# USB2JTAG.net
KiCad netlist of a schematic drawn in Altium Designer
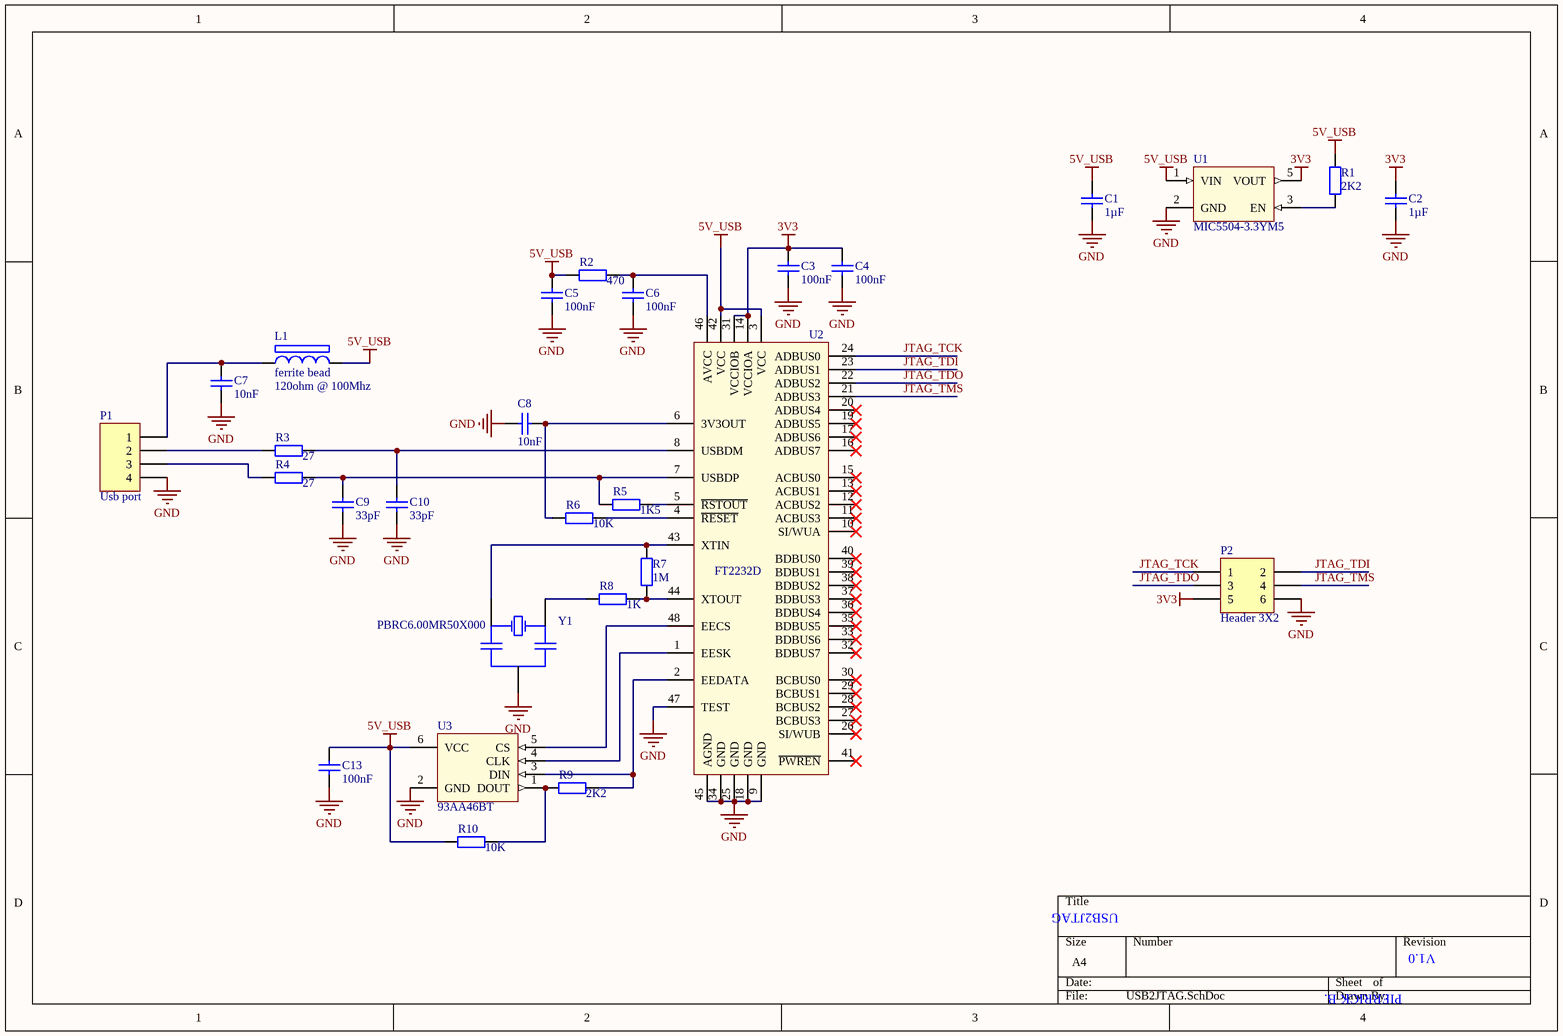
[diagram p0: USB2JTAG.SchDoc]

(export (version "E")
  (design (tool "Eeschema 10.0.6"))
  (components
    (comp (ref "C1")
      (value "1µF")
      (footprint "C0402")
      (description "Capacitor")
      (fields (field (name "Comment") "Cap") (field (name "PUBLISHER") "Altium Limited"))
      (libsource (lib "LIBRARY IGREBOT") (part "Cap"))
    )
    (comp (ref "C2")
      (value "1µF")
      (footprint "C0402")
      (description "Capacitor")
      (fields (field (name "Comment") "Cap") (field (name "PUBLISHER") "Altium Limited"))
      (libsource (lib "LIBRARY IGREBOT") (part "Cap"))
    )
    (comp (ref "C3")
      (value "100nF")
      (footprint "C0402")
      (description "Capacitor")
      (fields (field (name "Comment") "Cap") (field (name "PUBLISHER") "Altium Limited"))
      (libsource (lib "LIBRARY IGREBOT") (part "Cap"))
    )
    (comp (ref "C4")
      (value "100nF")
      (footprint "C0402")
      (description "Capacitor")
      (fields (field (name "Comment") "Cap") (field (name "PUBLISHER") "Altium Limited"))
      (libsource (lib "LIBRARY IGREBOT") (part "Cap"))
    )
    (comp (ref "C5")
      (value "100nF")
      (footprint "C0402")
      (description "Capacitor")
      (fields (field (name "Comment") "Cap") (field (name "PUBLISHER") "Altium Limited"))
      (libsource (lib "LIBRARY IGREBOT") (part "Cap"))
    )
    (comp (ref "C6")
      (value "100nF")
      (footprint "C0402")
      (description "Capacitor")
      (fields (field (name "Comment") "Cap") (field (name "PUBLISHER") "Altium Limited"))
      (libsource (lib "LIBRARY IGREBOT") (part "Cap"))
    )
    (comp (ref "C7")
      (value "10nF")
      (footprint "C0402")
      (description "Capacitor")
      (fields (field (name "Comment") "Cap") (field (name "PUBLISHER") "Altium Limited"))
      (libsource (lib "LIBRARY IGREBOT") (part "Cap"))
    )
    (comp (ref "C8")
      (value "10nF")
      (footprint "C0402")
      (description "Capacitor")
      (fields (field (name "Comment") "Cap") (field (name "PUBLISHER") "Altium Limited"))
      (libsource (lib "LIBRARY IGREBOT") (part "Cap"))
    )
    (comp (ref "C9")
      (value "33pF")
      (footprint "C0402")
      (description "Capacitor")
      (fields (field (name "Comment") "Cap") (field (name "PUBLISHER") "Altium Limited"))
      (libsource (lib "LIBRARY IGREBOT") (part "Cap"))
    )
    (comp (ref "C10")
      (value "33pF")
      (footprint "C0402")
      (description "Capacitor")
      (fields (field (name "Comment") "Cap") (field (name "PUBLISHER") "Altium Limited"))
      (libsource (lib "LIBRARY IGREBOT") (part "Cap"))
    )
    (comp (ref "C13")
      (value "100nF")
      (footprint "C0402")
      (description "Capacitor")
      (fields (field (name "Comment") "Cap") (field (name "PUBLISHER") "Altium Limited"))
      (libsource (lib "LIBRARY IGREBOT") (part "Cap"))
    )
    (comp (ref "L1")
      (value "ferrite bead")
      (footprint "0402")
      (fields (field (name "ALTIUM_VALUE") "120ohm @ 100Mhz") (field (name "PUBLISHER") "Altium Limited"))
      (libsource (lib "LIBRARY IGREBOT") (part "ferrite bead"))
    )
    (comp (ref "P1")
      (value "Usb port")
      (footprint "480371000")
      (libsource (lib "LIBRARY IGREBOT") (part "Usb port"))
    )
    (comp (ref "P2")
      (value "Header 3X2")
      (footprint "minitek127-6way")
      (description "Header, 6-Pin, Dual row")
      (fields (field (name "PUBLISHER") "Altium Limited"))
      (libsource (lib "LIBRARY IGREBOT") (part "Header 3X2"))
    )
    (comp (ref "R1")
      (value "2K2")
      (footprint "0402")
      (description "Resistor")
      (fields (field (name "Comment") "Res2") (field (name "PUBLISHER") "Altium Limited"))
      (libsource (lib "") (part "Res2_1"))
    )
    (comp (ref "R2")
      (value "470")
      (footprint "0402")
      (description "Resistor")
      (fields (field (name "Comment") "Res2") (field (name "PUBLISHER") "Altium Limited"))
      (libsource (lib "LIBRARY IGREBOT") (part "Res2"))
    )
    (comp (ref "R3")
      (value "27")
      (footprint "0402")
      (description "Resistor")
      (fields (field (name "Comment") "Res2") (field (name "PUBLISHER") "Altium Limited"))
      (libsource (lib "LIBRARY IGREBOT") (part "Res2"))
    )
    (comp (ref "R4")
      (value "27")
      (footprint "0402")
      (description "Resistor")
      (fields (field (name "Comment") "Res2") (field (name "PUBLISHER") "Altium Limited"))
      (libsource (lib "LIBRARY IGREBOT") (part "Res2"))
    )
    (comp (ref "R5")
      (value "1K5")
      (footprint "0402")
      (description "Resistor")
      (fields (field (name "Comment") "Res2") (field (name "PUBLISHER") "Altium Limited"))
      (libsource (lib "") (part "Res2_2"))
    )
    (comp (ref "R6")
      (value "10K")
      (footprint "0402")
      (description "Resistor")
      (fields (field (name "Comment") "Res2") (field (name "PUBLISHER") "Altium Limited"))
      (libsource (lib "LIBRARY IGREBOT") (part "Res2"))
    )
    (comp (ref "R7")
      (value "1M")
      (footprint "0402")
      (description "Resistor")
      (fields (field (name "Comment") "Res2") (field (name "PUBLISHER") "Altium Limited"))
      (libsource (lib "") (part "Res2_1"))
    )
    (comp (ref "R8")
      (value "1K")
      (footprint "0402")
      (description "Resistor")
      (fields (field (name "Comment") "Res2") (field (name "PUBLISHER") "Altium Limited"))
      (libsource (lib "LIBRARY IGREBOT") (part "Res2"))
    )
    (comp (ref "R9")
      (value "2K2")
      (footprint "0402")
      (description "Resistor")
      (fields (field (name "Comment") "Res2") (field (name "PUBLISHER") "Altium Limited"))
      (libsource (lib "LIBRARY IGREBOT") (part "Res2"))
    )
    (comp (ref "R10")
      (value "10K")
      (footprint "0402")
      (description "Resistor")
      (fields (field (name "Comment") "Res2") (field (name "PUBLISHER") "Altium Limited"))
      (libsource (lib "LIBRARY IGREBOT") (part "Res2"))
    )
    (comp (ref "U1")
      (value "MIC5504-3.3YM5")
      (footprint "SOT23-5_M")
      (libsource (lib "LIBRARY IGREBOT") (part "MIC5504-3.3YM5"))
    )
    (comp (ref "U2")
      (value "FT2232D")
      (footprint "LQFP-48")
      (libsource (lib "LIBRARY IGREBOT") (part "FT2232D"))
    )
    (comp (ref "U3")
      (value "93AA46BT")
      (footprint "SOT23-6_M")
      (libsource (lib "LIBRARY IGREBOT") (part "93AA46BT"))
    )
    (comp (ref "Y1")
      (value "PBRC6.00MR50X000")
      (footprint "PBRC_M")
      (libsource (lib "LIBRARY IGREBOT") (part "PBRC12.00HR50X0RZ"))
    )
  )
  (nets
    (net (code "1") (name "/JTAG_TCK") (class "Default")
      (node (ref "P2") (pin "1") (pinfunction "1_1") (pintype "passive"))
      (node (ref "U2") (pin "24") (pinfunction "ADBUS0_24") (pintype "passive"))
    )
    (net (code "2") (name "/JTAG_TDI") (class "Default")
      (node (ref "P2") (pin "2") (pinfunction "2_2") (pintype "passive"))
      (node (ref "U2") (pin "23") (pinfunction "ADBUS1_23") (pintype "passive"))
    )
    (net (code "3") (name "/JTAG_TDO") (class "Default")
      (node (ref "P2") (pin "3") (pinfunction "3_3") (pintype "passive"))
      (node (ref "U2") (pin "22") (pinfunction "ADBUS2_22") (pintype "passive"))
    )
    (net (code "4") (name "/JTAG_TMS") (class "Default")
      (node (ref "P2") (pin "4") (pinfunction "4_4") (pintype "passive"))
      (node (ref "U2") (pin "21") (pinfunction "ADBUS3_21") (pintype "passive"))
    )
    (net (code "5") (name "3V3") (class "Default")
      (node (ref "C2") (pin "1") (pinfunction "1_1") (pintype "passive"))
      (node (ref "C3") (pin "1") (pinfunction "1_1") (pintype "passive"))
      (node (ref "C4") (pin "1") (pinfunction "1_1") (pintype "passive"))
      (node (ref "P2") (pin "5") (pinfunction "5_5") (pintype "passive"))
      (node (ref "U1") (pin "5") (pinfunction "VOUT_5") (pintype "output"))
      (node (ref "U2") (pin "14") (pinfunction "VCCIOA_14") (pintype "passive"))
      (node (ref "U2") (pin "31") (pinfunction "VCCIOB_31") (pintype "passive"))
    )
    (net (code "6") (name "5V_USB") (class "Default")
      (node (ref "C1") (pin "1") (pinfunction "1_1") (pintype "passive"))
      (node (ref "C13") (pin "1") (pinfunction "1_1") (pintype "passive"))
      (node (ref "C5") (pin "1") (pinfunction "1_1") (pintype "passive"))
      (node (ref "L1") (pin "2") (pinfunction "2_2") (pintype "passive"))
      (node (ref "R1") (pin "2") (pinfunction "2_2") (pintype "passive"))
      (node (ref "R10") (pin "1") (pinfunction "1_1") (pintype "passive"))
      (node (ref "R2") (pin "1") (pinfunction "1_1") (pintype "passive"))
      (node (ref "U1") (pin "1") (pinfunction "VIN_1") (pintype "input"))
      (node (ref "U2") (pin "3") (pinfunction "VCC_3") (pintype "passive"))
      (node (ref "U2") (pin "42") (pinfunction "VCC_42") (pintype "passive"))
      (node (ref "U3") (pin "6") (pinfunction "VCC_6") (pintype "power_in"))
    )
    (net (code "7") (name "GND") (class "Default")
      (node (ref "C1") (pin "2") (pinfunction "2_2") (pintype "passive"))
      (node (ref "C10") (pin "2") (pinfunction "2_2") (pintype "passive"))
      (node (ref "C13") (pin "2") (pinfunction "2_2") (pintype "passive"))
      (node (ref "C2") (pin "2") (pinfunction "2_2") (pintype "passive"))
      (node (ref "C3") (pin "2") (pinfunction "2_2") (pintype "passive"))
      (node (ref "C4") (pin "2") (pinfunction "2_2") (pintype "passive"))
      (node (ref "C5") (pin "2") (pinfunction "2_2") (pintype "passive"))
      (node (ref "C6") (pin "2") (pinfunction "2_2") (pintype "passive"))
      (node (ref "C7") (pin "2") (pinfunction "2_2") (pintype "passive"))
      (node (ref "C8") (pin "2") (pinfunction "2_2") (pintype "passive"))
      (node (ref "C9") (pin "2") (pinfunction "2_2") (pintype "passive"))
      (node (ref "P1") (pin "4") (pinfunction "4_4") (pintype "passive"))
      (node (ref "P2") (pin "6") (pinfunction "6_6") (pintype "passive"))
      (node (ref "U1") (pin "2") (pinfunction "GND_2") (pintype "power_in"))
      (node (ref "U2") (pin "18") (pinfunction "GND_18") (pintype "passive"))
      (node (ref "U2") (pin "25") (pinfunction "GND_25") (pintype "passive"))
      (node (ref "U2") (pin "34") (pinfunction "GND_34") (pintype "passive"))
      (node (ref "U2") (pin "45") (pinfunction "AGND_45") (pintype "passive"))
      (node (ref "U2") (pin "47") (pinfunction "TEST_47") (pintype "passive"))
      (node (ref "U2") (pin "9") (pinfunction "GND_9") (pintype "passive"))
      (node (ref "U3") (pin "2") (pinfunction "GND_2") (pintype "passive"))
      (node (ref "Y1") (pin "2") (pinfunction "GND_2") (pintype "passive"))
    )
    (net (code "8") (name "Net-(C7-Pad1)") (class "Default")
      (node (ref "C7") (pin "1") (pinfunction "1_1") (pintype "passive"))
      (node (ref "L1") (pin "1") (pinfunction "1_1") (pintype "passive"))
      (node (ref "P1") (pin "1") (pinfunction "1_1") (pintype "passive"))
    )
    (net (code "9") (name "Net-(P1-Pad2)") (class "Default")
      (node (ref "P1") (pin "2") (pinfunction "2_2") (pintype "passive"))
      (node (ref "R3") (pin "1") (pinfunction "1_1") (pintype "passive"))
    )
    (net (code "10") (name "Net-(P1-Pad3)") (class "Default")
      (node (ref "P1") (pin "3") (pinfunction "3_3") (pintype "passive"))
      (node (ref "R4") (pin "1") (pinfunction "1_1") (pintype "passive"))
    )
    (net (code "11") (name "Net-(U1-EN)") (class "Default")
      (node (ref "R1") (pin "1") (pinfunction "1_1") (pintype "passive"))
      (node (ref "U1") (pin "3") (pinfunction "EN_3") (pintype "input"))
    )
    (net (code "12") (name "Net-(U2-3V3OUT)") (class "Default")
      (node (ref "C8") (pin "1") (pinfunction "1_1") (pintype "passive"))
      (node (ref "R6") (pin "1") (pinfunction "1_1") (pintype "passive"))
      (node (ref "U2") (pin "6") (pinfunction "3V3OUT_6") (pintype "passive"))
    )
    (net (code "13") (name "Net-(U2-AVCC)") (class "Default")
      (node (ref "C6") (pin "1") (pinfunction "1_1") (pintype "passive"))
      (node (ref "R2") (pin "2") (pinfunction "2_2") (pintype "passive"))
      (node (ref "U2") (pin "46") (pinfunction "AVCC_46") (pintype "passive"))
    )
    (net (code "14") (name "Net-(U2-EECS)") (class "Default")
      (node (ref "U2") (pin "48") (pinfunction "EECS_48") (pintype "passive"))
      (node (ref "U3") (pin "5") (pinfunction "CS_5") (pintype "input"))
    )
    (net (code "15") (name "Net-(U2-EEDATA)") (class "Default")
      (node (ref "R9") (pin "2") (pinfunction "2_2") (pintype "passive"))
      (node (ref "U2") (pin "2") (pinfunction "EEDATA_2") (pintype "passive"))
      (node (ref "U3") (pin "3") (pinfunction "DIN_3") (pintype "input"))
    )
    (net (code "16") (name "Net-(U2-EESK)") (class "Default")
      (node (ref "U2") (pin "1") (pinfunction "EESK_1") (pintype "passive"))
      (node (ref "U3") (pin "4") (pinfunction "CLK_4") (pintype "input"))
    )
    (net (code "17") (name "Net-(U2-USBDM)") (class "Default")
      (node (ref "C10") (pin "1") (pinfunction "1_1") (pintype "passive"))
      (node (ref "R3") (pin "2") (pinfunction "2_2") (pintype "passive"))
      (node (ref "U2") (pin "8") (pinfunction "USBDM_8") (pintype "passive"))
    )
    (net (code "18") (name "Net-(U2-USBDP)") (class "Default")
      (node (ref "C9") (pin "1") (pinfunction "1_1") (pintype "passive"))
      (node (ref "R4") (pin "2") (pinfunction "2_2") (pintype "passive"))
      (node (ref "R5") (pin "2") (pinfunction "2_2") (pintype "passive"))
      (node (ref "U2") (pin "7") (pinfunction "USBDP_7") (pintype "passive"))
    )
    (net (code "19") (name "Net-(U2-XTIN)") (class "Default")
      (node (ref "R7") (pin "2") (pinfunction "2_2") (pintype "passive"))
      (node (ref "U2") (pin "43") (pinfunction "XTIN_43") (pintype "passive"))
      (node (ref "Y1") (pin "1") (pinfunction "In_1") (pintype "passive"))
    )
    (net (code "20") (name "Net-(U2-XTOUT)") (class "Default")
      (node (ref "R7") (pin "1") (pinfunction "1_1") (pintype "passive"))
      (node (ref "R8") (pin "2") (pinfunction "2_2") (pintype "passive"))
      (node (ref "U2") (pin "44") (pinfunction "XTOUT_44") (pintype "passive"))
    )
    (net (code "21") (name "Net-(U2-~{RESET})") (class "Default")
      (node (ref "R6") (pin "2") (pinfunction "2_2") (pintype "passive"))
      (node (ref "U2") (pin "4") (pinfunction "~{RESET}_4") (pintype "passive"))
    )
    (net (code "22") (name "Net-(U2-~{RSTOUT})") (class "Default")
      (node (ref "R5") (pin "1") (pinfunction "1_1") (pintype "passive"))
      (node (ref "U2") (pin "5") (pinfunction "~{RSTOUT}_5") (pintype "passive"))
    )
    (net (code "23") (name "Net-(U3-DOUT)") (class "Default")
      (node (ref "R10") (pin "2") (pinfunction "2_2") (pintype "passive"))
      (node (ref "R9") (pin "1") (pinfunction "1_1") (pintype "passive"))
      (node (ref "U3") (pin "1") (pinfunction "DOUT_1") (pintype "output"))
    )
    (net (code "24") (name "Net-(Y1-Out)") (class "Default")
      (node (ref "R8") (pin "1") (pinfunction "1_1") (pintype "passive"))
      (node (ref "Y1") (pin "3") (pinfunction "Out_3") (pintype "passive"))
    )
    (net (code "25") (name "unconnected-(U2-ACBUS0-Pad15)") (class "Default")
      (node (ref "U2") (pin "15") (pinfunction "ACBUS0_15") (pintype "passive+no_connect"))
    )
    (net (code "26") (name "unconnected-(U2-ACBUS1-Pad13)") (class "Default")
      (node (ref "U2") (pin "13") (pinfunction "ACBUS1_13") (pintype "passive+no_connect"))
    )
    (net (code "27") (name "unconnected-(U2-ACBUS2-Pad12)") (class "Default")
      (node (ref "U2") (pin "12") (pinfunction "ACBUS2_12") (pintype "passive+no_connect"))
    )
    (net (code "28") (name "unconnected-(U2-ACBUS3-Pad11)") (class "Default")
      (node (ref "U2") (pin "11") (pinfunction "ACBUS3_11") (pintype "passive+no_connect"))
    )
    (net (code "29") (name "unconnected-(U2-ADBUS4-Pad20)") (class "Default")
      (node (ref "U2") (pin "20") (pinfunction "ADBUS4_20") (pintype "passive+no_connect"))
    )
    (net (code "30") (name "unconnected-(U2-ADBUS5-Pad19)") (class "Default")
      (node (ref "U2") (pin "19") (pinfunction "ADBUS5_19") (pintype "passive+no_connect"))
    )
    (net (code "31") (name "unconnected-(U2-ADBUS6-Pad17)") (class "Default")
      (node (ref "U2") (pin "17") (pinfunction "ADBUS6_17") (pintype "passive+no_connect"))
    )
    (net (code "32") (name "unconnected-(U2-ADBUS7-Pad16)") (class "Default")
      (node (ref "U2") (pin "16") (pinfunction "ADBUS7_16") (pintype "passive+no_connect"))
    )
    (net (code "33") (name "unconnected-(U2-BCBUS0-Pad30)") (class "Default")
      (node (ref "U2") (pin "30") (pinfunction "BCBUS0_30") (pintype "passive+no_connect"))
    )
    (net (code "34") (name "unconnected-(U2-BCBUS1-Pad29)") (class "Default")
      (node (ref "U2") (pin "29") (pinfunction "BCBUS1_29") (pintype "passive+no_connect"))
    )
    (net (code "35") (name "unconnected-(U2-BCBUS2-Pad28)") (class "Default")
      (node (ref "U2") (pin "28") (pinfunction "BCBUS2_28") (pintype "passive+no_connect"))
    )
    (net (code "36") (name "unconnected-(U2-BCBUS3-Pad27)") (class "Default")
      (node (ref "U2") (pin "27") (pinfunction "BCBUS3_27") (pintype "passive+no_connect"))
    )
    (net (code "37") (name "unconnected-(U2-BDBUS0-Pad40)") (class "Default")
      (node (ref "U2") (pin "40") (pinfunction "BDBUS0_40") (pintype "passive+no_connect"))
    )
    (net (code "38") (name "unconnected-(U2-BDBUS1-Pad39)") (class "Default")
      (node (ref "U2") (pin "39") (pinfunction "BDBUS1_39") (pintype "passive+no_connect"))
    )
    (net (code "39") (name "unconnected-(U2-BDBUS2-Pad38)") (class "Default")
      (node (ref "U2") (pin "38") (pinfunction "BDBUS2_38") (pintype "passive+no_connect"))
    )
    (net (code "40") (name "unconnected-(U2-BDBUS3-Pad37)") (class "Default")
      (node (ref "U2") (pin "37") (pinfunction "BDBUS3_37") (pintype "passive+no_connect"))
    )
    (net (code "41") (name "unconnected-(U2-BDBUS4-Pad36)") (class "Default")
      (node (ref "U2") (pin "36") (pinfunction "BDBUS4_36") (pintype "passive+no_connect"))
    )
    (net (code "42") (name "unconnected-(U2-BDBUS5-Pad35)") (class "Default")
      (node (ref "U2") (pin "35") (pinfunction "BDBUS5_35") (pintype "passive+no_connect"))
    )
    (net (code "43") (name "unconnected-(U2-BDBUS6-Pad33)") (class "Default")
      (node (ref "U2") (pin "33") (pinfunction "BDBUS6_33") (pintype "passive+no_connect"))
    )
    (net (code "44") (name "unconnected-(U2-BDBUS7-Pad32)") (class "Default")
      (node (ref "U2") (pin "32") (pinfunction "BDBUS7_32") (pintype "passive+no_connect"))
    )
    (net (code "45") (name "unconnected-(U2-SI{slash}WUA-Pad10)") (class "Default")
      (node (ref "U2") (pin "10") (pinfunction "SI/WUA_10") (pintype "passive+no_connect"))
    )
    (net (code "46") (name "unconnected-(U2-SI{slash}WUB-Pad26)") (class "Default")
      (node (ref "U2") (pin "26") (pinfunction "SI/WUB_26") (pintype "passive+no_connect"))
    )
    (net (code "47") (name "unconnected-(U2-~{PWREN}-Pad41)") (class "Default")
      (node (ref "U2") (pin "41") (pinfunction "~{PWREN}_41") (pintype "passive+no_connect"))
    )
  )
)
